# Harp_Motor_H2-module_v1_0.net
KiCad netlist of a schematic drawn in EAGLE
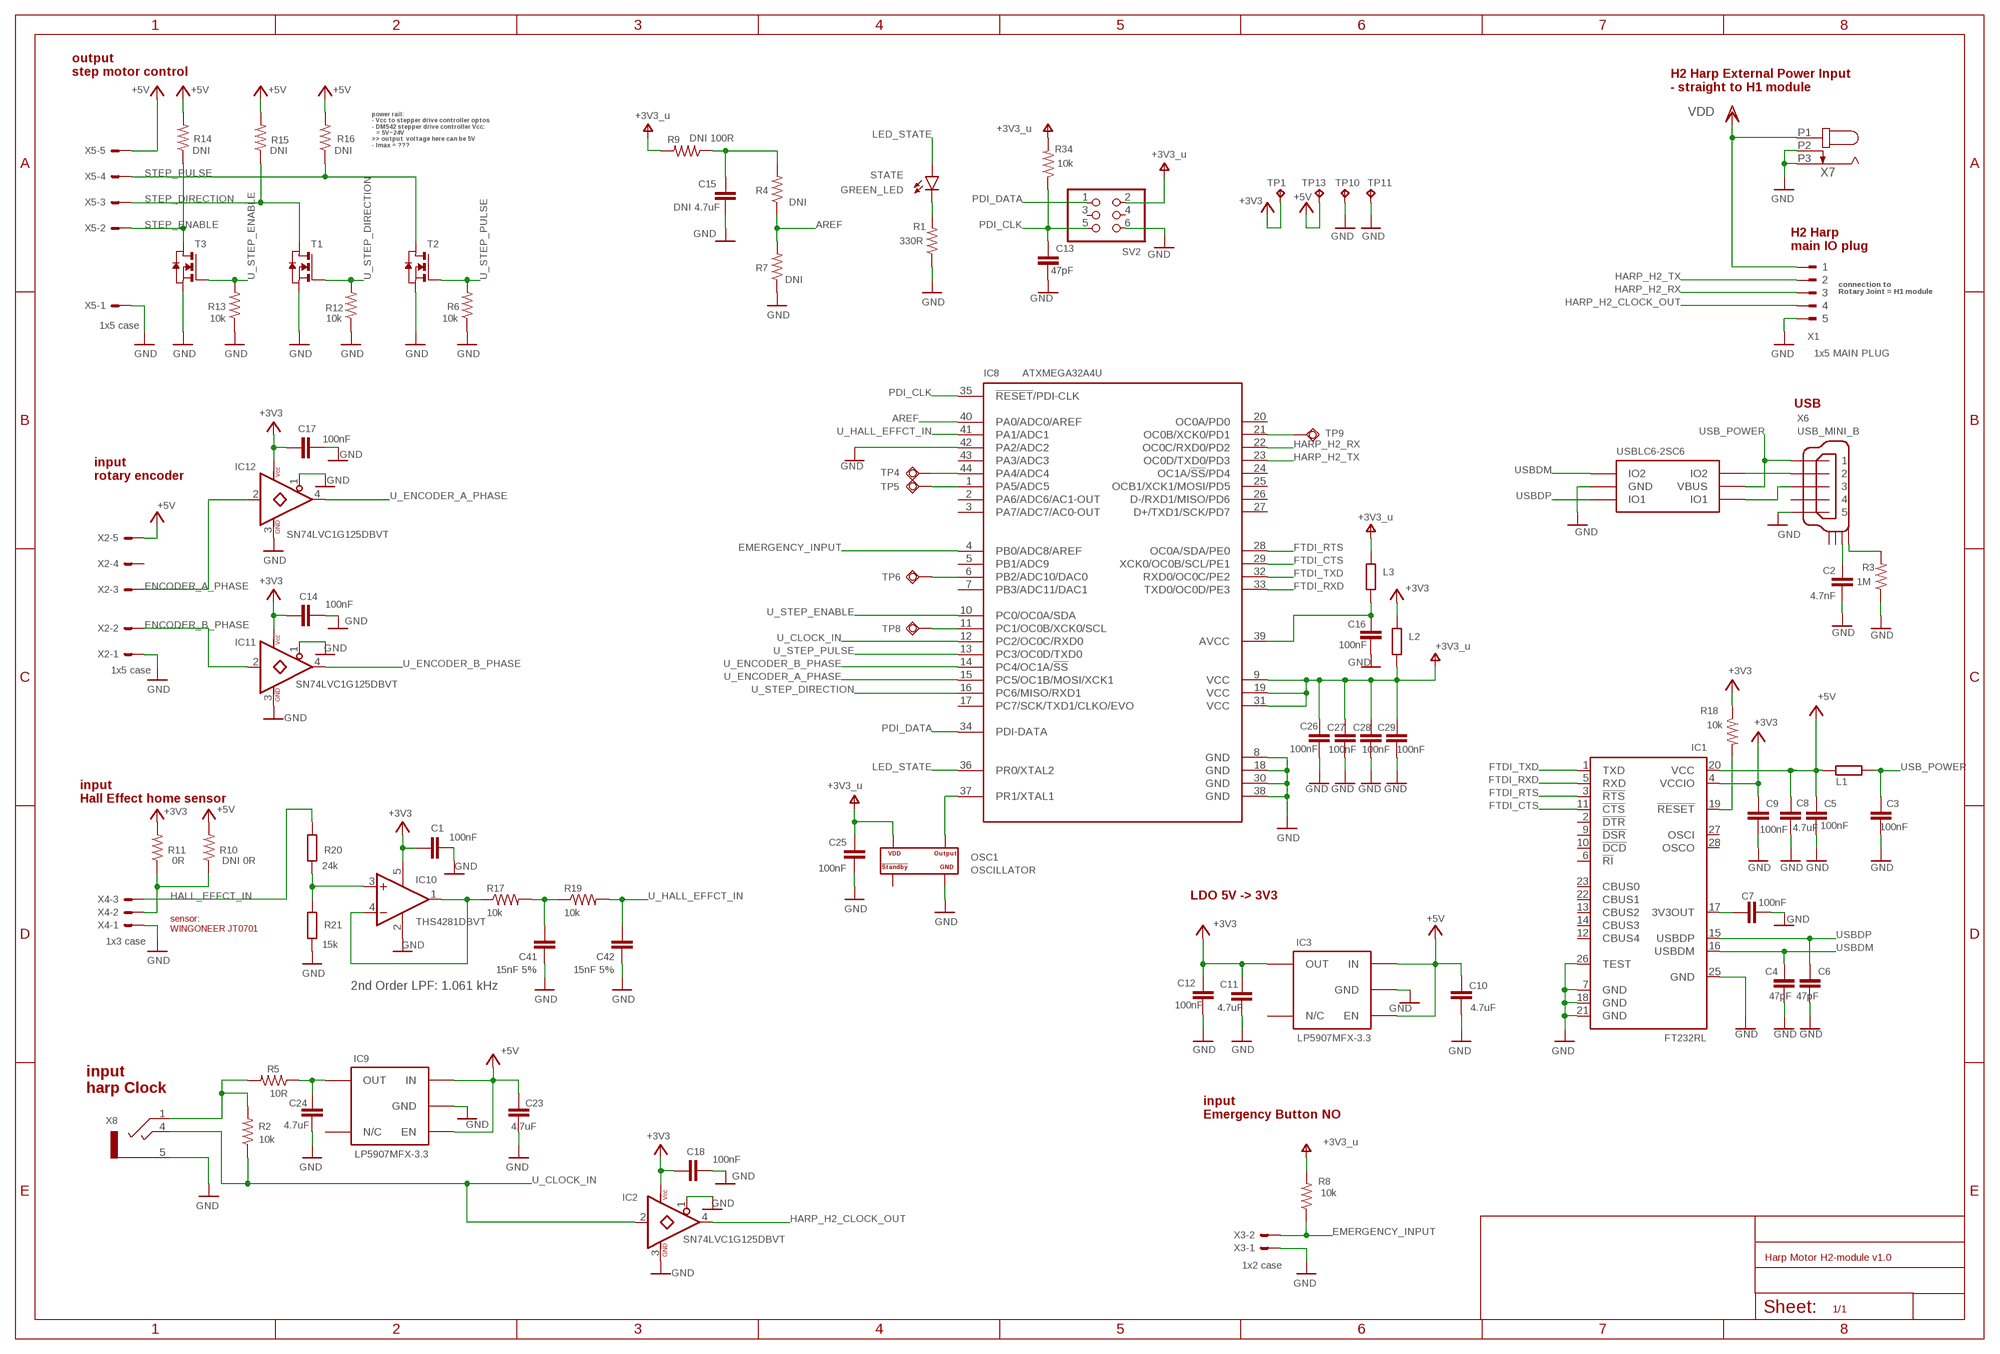
[diagram p0: schematic, sheet 1]

(export (version "E")
  (design (tool "Eeschema 10.0.6"))
  (components
    (comp (ref "C1")
      (value "100nF")
      (footprint "eagle-import:C0402K")
      (fields (field (name "MPN") "C1005X7R1H104K050BB"))
      (libsource (lib "eagle-import") (part "C-EUC0402K"))
    )
    (comp (ref "C2")
      (value "4.7nF")
      (footprint "eagle-import:C0402K")
      (fields (field (name "MPN") "CC0402KRX7R8BB472"))
      (libsource (lib "eagle-import") (part "C-EUC0402K"))
    )
    (comp (ref "C3")
      (value "100nF")
      (footprint "eagle-import:C0402K")
      (fields (field (name "MPN") "C1005X7R1H104K050BB"))
      (libsource (lib "eagle-import") (part "C-EUC0402K"))
    )
    (comp (ref "C4")
      (value "47pF")
      (footprint "eagle-import:C0402K")
      (fields (field (name "MPN") "04025A470JAT2A"))
      (libsource (lib "eagle-import") (part "C-EUC0402K"))
    )
    (comp (ref "C5")
      (value "100nF")
      (footprint "eagle-import:C0402K")
      (fields (field (name "MPN") "C1005X7R1H104K050BB"))
      (libsource (lib "eagle-import") (part "C-EUC0402K"))
    )
    (comp (ref "C6")
      (value "47pF")
      (footprint "eagle-import:C0402K")
      (fields (field (name "MPN") "04025A470JAT2A"))
      (libsource (lib "eagle-import") (part "C-EUC0402K"))
    )
    (comp (ref "C7")
      (value "100nF")
      (footprint "eagle-import:C0402K")
      (fields (field (name "MPN") "C1005X7R1H104K050BB"))
      (libsource (lib "eagle-import") (part "C-EUC0402K"))
    )
    (comp (ref "C8")
      (value "4.7uF")
      (footprint "eagle-import:C0603K")
      (fields (field (name "MPN") "C1608X6S1C475K080AC"))
      (libsource (lib "eagle-import") (part "C-EUC0603K"))
    )
    (comp (ref "C9")
      (value "100nF")
      (footprint "eagle-import:C0402K")
      (fields (field (name "MPN") "C1005X7R1H104K050BB"))
      (libsource (lib "eagle-import") (part "C-EUC0402K"))
    )
    (comp (ref "C10")
      (value "4.7uF")
      (footprint "eagle-import:C0603K")
      (fields (field (name "MPN") "C1608X6S1C475K080AC"))
      (libsource (lib "eagle-import") (part "C-EUC0603K"))
    )
    (comp (ref "C11")
      (value "4.7uF")
      (footprint "eagle-import:C0603K")
      (fields (field (name "MPN") "C1608X6S1C475K080AC"))
      (libsource (lib "eagle-import") (part "C-EUC0603K"))
    )
    (comp (ref "C12")
      (value "100nF")
      (footprint "eagle-import:C0402K")
      (fields (field (name "MPN") "C1005X7R1H104K050BB"))
      (libsource (lib "eagle-import") (part "C-EUC0402K"))
    )
    (comp (ref "C13")
      (value "47pF")
      (footprint "eagle-import:C0402K")
      (fields (field (name "MPN") "04025A470JAT2A"))
      (libsource (lib "eagle-import") (part "C-EUC0402K"))
    )
    (comp (ref "C14")
      (value "100nF")
      (footprint "eagle-import:C0402K")
      (fields (field (name "MPN") "C1005X7R1H104K050BB"))
      (libsource (lib "eagle-import") (part "C-EUC0402K"))
    )
    (comp (ref "C15")
      (value "DNI 4.7uF")
      (footprint "eagle-import:C0603K")
      (fields (field (name "MPN") "C1608X6S1C475K080AC"))
      (libsource (lib "eagle-import") (part "C-EUC0603K"))
    )
    (comp (ref "C16")
      (value "100nF")
      (footprint "eagle-import:C0402K")
      (fields (field (name "MPN") "C1005X7R1H104K050BB"))
      (libsource (lib "eagle-import") (part "C-EUC0402K"))
    )
    (comp (ref "C17")
      (value "100nF")
      (footprint "eagle-import:C0402K")
      (fields (field (name "MPN") "C1005X7R1H104K050BB"))
      (libsource (lib "eagle-import") (part "C-EUC0402K"))
    )
    (comp (ref "C18")
      (value "100nF")
      (footprint "eagle-import:C0402K")
      (fields (field (name "MPN") "C1005X7R1H104K050BB"))
      (libsource (lib "eagle-import") (part "C-EUC0402K"))
    )
    (comp (ref "C23")
      (value "4.7uF")
      (footprint "eagle-import:C0603K")
      (fields (field (name "MPN") "C1608X6S1C475K080AC"))
      (libsource (lib "eagle-import") (part "C-EUC0603K"))
    )
    (comp (ref "C24")
      (value "4.7uF")
      (footprint "eagle-import:C0603K")
      (fields (field (name "MPN") "C1608X6S1C475K080AC"))
      (libsource (lib "eagle-import") (part "C-EUC0603K"))
    )
    (comp (ref "C25")
      (value "100nF")
      (footprint "eagle-import:C0402K")
      (fields (field (name "MPN") "C1005X7R1H104K050BB"))
      (libsource (lib "eagle-import") (part "C-EUC0402K"))
    )
    (comp (ref "C26")
      (value "100nF")
      (footprint "eagle-import:C0402K")
      (fields (field (name "MPN") "C1005X7R1H104K050BB"))
      (libsource (lib "eagle-import") (part "C-EUC0402K"))
    )
    (comp (ref "C27")
      (value "100nF")
      (footprint "eagle-import:C0402K")
      (fields (field (name "MPN") "C1005X7R1H104K050BB"))
      (libsource (lib "eagle-import") (part "C-EUC0402K"))
    )
    (comp (ref "C28")
      (value "100nF")
      (footprint "eagle-import:C0402K")
      (fields (field (name "MPN") "C1005X7R1H104K050BB"))
      (libsource (lib "eagle-import") (part "C-EUC0402K"))
    )
    (comp (ref "C29")
      (value "100nF")
      (footprint "eagle-import:C0402K")
      (fields (field (name "MPN") "C1005X7R1H104K050BB"))
      (libsource (lib "eagle-import") (part "C-EUC0402K"))
    )
    (comp (ref "C41")
      (value "15nF 5%")
      (footprint "eagle-import:C0402K")
      (fields (field (name "MPN") "CGA2B3X7R1V153K050BB"))
      (libsource (lib "eagle-import") (part "C-EUC0402K"))
    )
    (comp (ref "C42")
      (value "15nF 5%")
      (footprint "eagle-import:C0402K")
      (fields (field (name "MPN") "CGA2B3X7R1V153K050BB"))
      (libsource (lib "eagle-import") (part "C-EUC0402K"))
    )
    (comp (ref "IC1")
      (value "FT232RL")
      (footprint "eagle-import:SSOP28")
      (libsource (lib "eagle-import") (part "FT232RL"))
    )
    (comp (ref "IC2")
      (value "SN74LVC1G125DBVT")
      (footprint "eagle-import:SOT23-5")
      (libsource (lib "eagle-import") (part "741G125DBVLVC"))
    )
    (comp (ref "IC3")
      (value "LP5907MFX-3.3")
      (footprint "eagle-import:TSOT23-5")
      (fields (field (name "MPN") "LP5907MFX-3.3/NOPB"))
      (libsource (lib "eagle-import") (part "TLV700XX"))
    )
    (comp (ref "IC7")
      (value "USBLC6-2SC6")
      (footprint "eagle-import:SOT23-6L")
      (libsource (lib "eagle-import") (part "USBLC6-2SC6"))
    )
    (comp (ref "IC8")
      (value "ATXMEGA32A4U")
      (footprint "eagle-import:TQFP44")
      (fields (field (name "MPN") "ATXMEGA32A4U-AUR"))
      (libsource (lib "eagle-import") (part "XMEGA-A4_AT-XMEGA-XXA4-AUTQFP44"))
    )
    (comp (ref "IC9")
      (value "LP5907MFX-3.3")
      (footprint "eagle-import:TSOT23-5")
      (fields (field (name "MPN") "LP5907MFX-3.3/NOPB"))
      (libsource (lib "eagle-import") (part "TLV700XX"))
    )
    (comp (ref "IC10")
      (value "THS4281DBVT")
      (footprint "eagle-import:SOT23-5")
      (libsource (lib "eagle-import") (part "OPA365"))
    )
    (comp (ref "IC11")
      (value "SN74LVC1G125DBVT")
      (footprint "eagle-import:SOT23-5")
      (libsource (lib "eagle-import") (part "741G125DBVLVC"))
    )
    (comp (ref "IC12")
      (value "SN74LVC1G125DBVT")
      (footprint "eagle-import:SOT23-5")
      (libsource (lib "eagle-import") (part "741G125DBVLVC"))
    )
    (comp (ref "L1")
      (value "40R@100MHz")
      (footprint "eagle-import:R0805")
      (fields (field (name "MPN") "MI0805K400R-10"))
      (libsource (lib "eagle-import") (part "R-EU_R0805"))
    )
    (comp (ref "L2")
      (value "40R@100MHz")
      (footprint "eagle-import:R0805")
      (fields (field (name "MPN") "MI0805K400R-10"))
      (libsource (lib "eagle-import") (part "R-EU_R0805"))
    )
    (comp (ref "L3")
      (value "40R@100MHz")
      (footprint "eagle-import:R0805")
      (fields (field (name "MPN") "MI0805K400R-10"))
      (libsource (lib "eagle-import") (part "R-EU_R0805"))
    )
    (comp (ref "OSC1")
      (value "OSCILLATOR")
      (footprint "eagle-import:OSCILLATOR_3.2X2.5")
      (fields (field (name "MPN") "DSC1001CI5-032.0000"))
      (libsource (lib "eagle-import") (part "OSCILLATOR"))
    )
    (comp (ref "R1")
      (value "330R")
      (footprint "eagle-import:R0402")
      (fields (field (name "MPN") "RC0402FR-07330RL"))
      (libsource (lib "eagle-import") (part "R-US_R0402"))
    )
    (comp (ref "R2")
      (value "10k")
      (footprint "eagle-import:R0402")
      (fields (field (name "MPN") "CRCW040210K0FKED"))
      (libsource (lib "eagle-import") (part "R-US_R0402"))
    )
    (comp (ref "R3")
      (value "1M")
      (footprint "eagle-import:R0402")
      (fields (field (name "MPN") "CRCW04021M00FKED"))
      (libsource (lib "eagle-import") (part "R-US_R0402"))
    )
    (comp (ref "R4")
      (value "DNI")
      (footprint "eagle-import:R0402")
      (libsource (lib "eagle-import") (part "R-US_R0402"))
    )
    (comp (ref "R5")
      (value "10R")
      (footprint "eagle-import:R0402")
      (fields (field (name "MPN") "ERJ-PA2J100X "))
      (libsource (lib "eagle-import") (part "R-US_R0402"))
    )
    (comp (ref "R6")
      (value "10k")
      (footprint "eagle-import:R0402")
      (fields (field (name "MPN") "CRCW040210K0FKED"))
      (libsource (lib "eagle-import") (part "R-US_R0402"))
    )
    (comp (ref "R7")
      (value "DNI")
      (footprint "eagle-import:R0402")
      (libsource (lib "eagle-import") (part "R-US_R0402"))
    )
    (comp (ref "R8")
      (value "10k")
      (footprint "eagle-import:R0402")
      (fields (field (name "MPN") "CRCW040210K0FKED"))
      (libsource (lib "eagle-import") (part "R-US_R0402"))
    )
    (comp (ref "R9")
      (value "DNI 100R")
      (footprint "eagle-import:R0402")
      (fields (field (name "MPN") "ERJ-2RKF1000X "))
      (libsource (lib "eagle-import") (part "R-US_R0402"))
    )
    (comp (ref "R10")
      (value "DNI 0R")
      (footprint "eagle-import:R0402")
      (fields (field (name "MPN") "RC0402JR-070RL"))
      (libsource (lib "eagle-import") (part "R-US_R0402"))
    )
    (comp (ref "R11")
      (value "0R")
      (footprint "eagle-import:R0402")
      (fields (field (name "MPN") "RC0402JR-070RL"))
      (libsource (lib "eagle-import") (part "R-US_R0402"))
    )
    (comp (ref "R12")
      (value "10k")
      (footprint "eagle-import:R0402")
      (fields (field (name "MPN") "CRCW040210K0FKED"))
      (libsource (lib "eagle-import") (part "R-US_R0402"))
    )
    (comp (ref "R13")
      (value "10k")
      (footprint "eagle-import:R0402")
      (fields (field (name "MPN") "CRCW040210K0FKED"))
      (libsource (lib "eagle-import") (part "R-US_R0402"))
    )
    (comp (ref "R14")
      (value "DNI")
      (footprint "eagle-import:R0402")
      (libsource (lib "eagle-import") (part "R-US_R0402"))
    )
    (comp (ref "R15")
      (value "DNI")
      (footprint "eagle-import:R0402")
      (libsource (lib "eagle-import") (part "R-US_R0402"))
    )
    (comp (ref "R16")
      (value "DNI")
      (footprint "eagle-import:R0402")
      (libsource (lib "eagle-import") (part "R-US_R0402"))
    )
    (comp (ref "R17")
      (value "10k")
      (footprint "eagle-import:R0402")
      (fields (field (name "MPN") "CRCW040210K0FKED"))
      (libsource (lib "eagle-import") (part "R-US_R0402"))
    )
    (comp (ref "R18")
      (value "10k")
      (footprint "eagle-import:R0402")
      (fields (field (name "MPN") "CRCW040210K0FKED"))
      (libsource (lib "eagle-import") (part "R-US_R0402"))
    )
    (comp (ref "R19")
      (value "10k")
      (footprint "eagle-import:R0402")
      (fields (field (name "MPN") "CRCW040210K0FKED"))
      (libsource (lib "eagle-import") (part "R-US_R0402"))
    )
    (comp (ref "R20")
      (value "24k")
      (footprint "eagle-import:R0402")
      (fields (field (name "MPN") "ERJ-2RKF2402X"))
      (libsource (lib "eagle-import") (part "R-EU_R0402"))
    )
    (comp (ref "R21")
      (value "15k")
      (footprint "eagle-import:R0402")
      (fields (field (name "MPN") "ERJ-2RKF1502X"))
      (libsource (lib "eagle-import") (part "R-EU_R0402"))
    )
    (comp (ref "R34")
      (value "10k")
      (footprint "eagle-import:R0402")
      (fields (field (name "MPN") "CRCW040210K0FKED"))
      (libsource (lib "eagle-import") (part "R-US_R0402"))
    )
    (comp (ref "STATE")
      (value "GREEN_LED")
      (footprint "eagle-import:CHIP-LED0603")
      (fields (field (name "MPN") "LTST-C191KGKT"))
      (libsource (lib "eagle-import") (part "LEDCHIP-LED0603"))
    )
    (comp (ref "SV2")
      (value "PINHD-2X3")
      (footprint "eagle-import:2X03")
      (fields (field (name "MPN") "609-3210-ND"))
      (libsource (lib "eagle-import") (part "PINHD-2X3"))
    )
    (comp (ref "T1")
      (value "DMG1012UW")
      (footprint "eagle-import:SOT323")
      (fields (field (name "MPN") "DMG1012UW-7"))
      (libsource (lib "eagle-import") (part "DMG1012UW-7"))
    )
    (comp (ref "T2")
      (value "DMG1012UW")
      (footprint "eagle-import:SOT323")
      (fields (field (name "MPN") "DMG1012UW-7"))
      (libsource (lib "eagle-import") (part "DMG1012UW-7"))
    )
    (comp (ref "T3")
      (value "DMG1012UW")
      (footprint "eagle-import:SOT323")
      (fields (field (name "MPN") "DMG1012UW-7"))
      (libsource (lib "eagle-import") (part "DMG1012UW-7"))
    )
    (comp (ref "TP1")
      (value "NO_COMPONENT")
      (footprint "eagle-import:B1,27")
      (libsource (lib "eagle-import") (part "TPB1,27"))
    )
    (comp (ref "TP4")
      (value "NO_COMPONENT")
      (footprint "eagle-import:TP11R")
      (libsource (lib "eagle-import") (part "TPSQTP11R"))
    )
    (comp (ref "TP5")
      (value "NO_COMPONENT")
      (footprint "eagle-import:TP11R")
      (libsource (lib "eagle-import") (part "TPSQTP11R"))
    )
    (comp (ref "TP6")
      (value "NO_COMPONENT")
      (footprint "eagle-import:TP11R")
      (libsource (lib "eagle-import") (part "TPSQTP11R"))
    )
    (comp (ref "TP8")
      (value "NO_COMPONENT")
      (footprint "eagle-import:TP11R")
      (libsource (lib "eagle-import") (part "TPSQTP11R"))
    )
    (comp (ref "TP9")
      (value "NO_COMPONENT")
      (footprint "eagle-import:TP11R")
      (libsource (lib "eagle-import") (part "TPSQTP11R"))
    )
    (comp (ref "TP10")
      (value "NO_COMPONENT")
      (footprint "eagle-import:B1,27")
      (libsource (lib "eagle-import") (part "TPB1,27"))
    )
    (comp (ref "TP11")
      (value "NO_COMPONENT")
      (footprint "eagle-import:B1,27")
      (libsource (lib "eagle-import") (part "TPB1,27"))
    )
    (comp (ref "TP13")
      (value "NO_COMPONENT")
      (footprint "eagle-import:B1,27")
      (libsource (lib "eagle-import") (part "TPB1,27"))
    )
    (comp (ref "X1")
      (value "1x5 MAIN PLUG")
      (footprint "eagle-import:90G-5")
      (fields (field (name "MPN") "20.155MH/5-E"))
      (libsource (lib "eagle-import") (part "90G-5"))
    )
    (comp (ref "X2")
      (value "1x5 case")
      (footprint "eagle-import:22-23-2051")
      (fields (field (name "MPN") "282834-5") (field (name "OEPS") "OEPS070041"))
      (libsource (lib "eagle-import") (part "22-23-2051"))
    )
    (comp (ref "X3")
      (value "1x2 case")
      (footprint "eagle-import:22-23-2021")
      (fields (field (name "MPN") "282834-2"))
      (libsource (lib "eagle-import") (part "22-23-2021"))
    )
    (comp (ref "X4")
      (value "1x3 case")
      (footprint "eagle-import:22-23-2031")
      (fields (field (name "MPN") "282834-3") (field (name "OEPS") "OEPS070035"))
      (libsource (lib "eagle-import") (part "22-23-2031"))
    )
    (comp (ref "X5")
      (value "1x5 case")
      (footprint "eagle-import:22-23-2051")
      (fields (field (name "MPN") "282834-5") (field (name "OEPS") "OEPS070041"))
      (libsource (lib "eagle-import") (part "22-23-2051"))
    )
    (comp (ref "X6")
      (value "USB_MINI_B")
      (footprint "eagle-import:240-0002-1")
      (fields (field (name "MPN") "UX60-MB-5S8"))
      (libsource (lib "eagle-import") (part "USB_MINI_B"))
    )
    (comp (ref "X7")
      (value "DC_JACK2.1MM")
      (footprint "eagle-import:DC_POWER_INPUT_2.1MM")
      (fields (field (name "MPN") "163-179PH-EX"))
      (libsource (lib "eagle-import") (part "DC_JACK2.1MM"))
    )
    (comp (ref "X8")
      (value "CLCK_JACK")
      (footprint "eagle-import:35RASMT2BHNTRX")
      (fields (field (name "MPN") "35RASMT2BHNTRX"))
      (libsource (lib "eagle-import") (part "STEREO_JACK"))
    )
  )
  (nets
    (net (code "1") (name "+3V3") (class "Default")
      (node (ref "C1") (pin "1") (pinfunction "1_1") (pintype "passive"))
      (node (ref "C11") (pin "1") (pinfunction "1_1") (pintype "passive"))
      (node (ref "C12") (pin "1") (pinfunction "1_1") (pintype "passive"))
      (node (ref "C14") (pin "1") (pinfunction "1_1") (pintype "passive"))
      (node (ref "C17") (pin "1") (pinfunction "1_1") (pintype "passive"))
      (node (ref "C18") (pin "1") (pinfunction "1_1") (pintype "passive"))
      (node (ref "C9") (pin "1") (pinfunction "1_1") (pintype "passive"))
      (node (ref "IC1") (pin "4") (pinfunction "VCCIO_4") (pintype "power_in"))
      (node (ref "IC10") (pin "5") (pinfunction "V+_5") (pintype "power_in"))
      (node (ref "IC11") (pin "5") (pinfunction "VCC_5") (pintype "passive"))
      (node (ref "IC12") (pin "5") (pinfunction "VCC_5") (pintype "passive"))
      (node (ref "IC2") (pin "5") (pinfunction "VCC_5") (pintype "passive"))
      (node (ref "IC3") (pin "5") (pinfunction "OUT_5") (pintype "bidirectional"))
      (node (ref "L2") (pin "2") (pinfunction "2_2") (pintype "passive"))
      (node (ref "R11") (pin "2") (pinfunction "2_2") (pintype "passive"))
      (node (ref "R18") (pin "1") (pinfunction "1_1") (pintype "passive"))
      (node (ref "TP1") (pin "TP") (pinfunction "TP_TP") (pintype "input"))
    )
    (net (code "2") (name "+3V3_u") (class "Default")
      (node (ref "C25") (pin "1") (pinfunction "1_1") (pintype "passive"))
      (node (ref "C26") (pin "1") (pinfunction "1_1") (pintype "passive"))
      (node (ref "C27") (pin "1") (pinfunction "1_1") (pintype "passive"))
      (node (ref "C28") (pin "1") (pinfunction "1_1") (pintype "passive"))
      (node (ref "C29") (pin "1") (pinfunction "1_1") (pintype "passive"))
      (node (ref "IC8") (pin "19") (pinfunction "VCC_19") (pintype "power_in"))
      (node (ref "IC8") (pin "31") (pinfunction "VCC_31") (pintype "power_in"))
      (node (ref "IC8") (pin "9") (pinfunction "VCC_9") (pintype "power_in"))
      (node (ref "L2") (pin "1") (pinfunction "1_1") (pintype "passive"))
      (node (ref "L3") (pin "2") (pinfunction "2_2") (pintype "passive"))
      (node (ref "OSC1") (pin "P$4") (pinfunction "VDD_P$4") (pintype "passive"))
      (node (ref "R34") (pin "2") (pinfunction "2_2") (pintype "passive"))
      (node (ref "R8") (pin "2") (pinfunction "2_2") (pintype "passive"))
      (node (ref "R9") (pin "2") (pinfunction "2_2") (pintype "passive"))
      (node (ref "SV2") (pin "2") (pinfunction "2_2") (pintype "passive"))
    )
    (net (code "3") (name "+5V") (class "Default")
      (node (ref "C10") (pin "1") (pinfunction "1_1") (pintype "passive"))
      (node (ref "C23") (pin "1") (pinfunction "1_1") (pintype "passive"))
      (node (ref "C5") (pin "1") (pinfunction "1_1") (pintype "passive"))
      (node (ref "C8") (pin "1") (pinfunction "1_1") (pintype "passive"))
      (node (ref "IC1") (pin "20") (pinfunction "VCC_20") (pintype "power_in"))
      (node (ref "IC3") (pin "1") (pinfunction "IN_1") (pintype "bidirectional"))
      (node (ref "IC3") (pin "3") (pinfunction "EN_3") (pintype "bidirectional"))
      (node (ref "IC9") (pin "1") (pinfunction "IN_1") (pintype "bidirectional"))
      (node (ref "IC9") (pin "3") (pinfunction "EN_3") (pintype "bidirectional"))
      (node (ref "L1") (pin "1") (pinfunction "1_1") (pintype "passive"))
      (node (ref "R10") (pin "2") (pinfunction "2_2") (pintype "passive"))
      (node (ref "R14") (pin "2") (pinfunction "2_2") (pintype "passive"))
      (node (ref "R15") (pin "2") (pinfunction "2_2") (pintype "passive"))
      (node (ref "R16") (pin "2") (pinfunction "2_2") (pintype "passive"))
      (node (ref "TP13") (pin "TP") (pinfunction "TP_TP") (pintype "input"))
      (node (ref "X2") (pin "5") (pinfunction "S_5") (pintype "passive"))
      (node (ref "X5") (pin "5") (pinfunction "S_5") (pintype "passive"))
    )
    (net (code "4") (name "/AREF") (class "Default")
      (node (ref "IC8") (pin "40") (pinfunction "PA0/ADC0/AREF_40") (pintype "bidirectional"))
      (node (ref "R4") (pin "1") (pinfunction "1_1") (pintype "passive"))
      (node (ref "R7") (pin "2") (pinfunction "2_2") (pintype "passive"))
    )
    (net (code "5") (name "/EMERGENCY_INPUT") (class "Default")
      (node (ref "IC8") (pin "4") (pinfunction "PB0/ADC8/AREF_4") (pintype "bidirectional"))
      (node (ref "R8") (pin "1") (pinfunction "1_1") (pintype "passive"))
      (node (ref "X3") (pin "2") (pinfunction "S_2") (pintype "passive"))
    )
    (net (code "6") (name "/ENCODER_A_PHASE") (class "Default")
      (node (ref "IC12") (pin "2") (pinfunction "I_2") (pintype "input"))
      (node (ref "X2") (pin "3") (pinfunction "S_3") (pintype "passive"))
    )
    (net (code "7") (name "/ENCODER_B_PHASE") (class "Default")
      (node (ref "IC11") (pin "2") (pinfunction "I_2") (pintype "input"))
      (node (ref "X2") (pin "2") (pinfunction "S_2") (pintype "passive"))
    )
    (net (code "8") (name "/FTDI_CTS") (class "Default")
      (node (ref "IC1") (pin "11") (pinfunction "~{CTS}_11") (pintype "input"))
      (node (ref "IC8") (pin "29") (pinfunction "XCK0/OC0B/SCL/PE1_29") (pintype "bidirectional"))
    )
    (net (code "9") (name "/FTDI_RTS") (class "Default")
      (node (ref "IC1") (pin "3") (pinfunction "~{RTS}_3") (pintype "output"))
      (node (ref "IC8") (pin "28") (pinfunction "OC0A/SDA/PE0_28") (pintype "bidirectional"))
    )
    (net (code "10") (name "/FTDI_RXD") (class "Default")
      (node (ref "IC1") (pin "5") (pinfunction "RXD_5") (pintype "input"))
      (node (ref "IC8") (pin "33") (pinfunction "TXD0/OC0D/PE3_33") (pintype "bidirectional"))
    )
    (net (code "11") (name "/FTDI_TXD") (class "Default")
      (node (ref "IC1") (pin "1") (pinfunction "TXD_1") (pintype "output"))
      (node (ref "IC8") (pin "32") (pinfunction "RXD0/OC0C/PE2_32") (pintype "bidirectional"))
    )
    (net (code "12") (name "/HALL_EFFCT_IN") (class "Default")
      (node (ref "R20") (pin "2") (pinfunction "2_2") (pintype "passive"))
      (node (ref "X4") (pin "3") (pinfunction "S_3") (pintype "passive"))
    )
    (net (code "13") (name "/HARP_H2_CLOCK_OUT") (class "Default")
      (node (ref "IC2") (pin "4") (pinfunction "O_4") (pintype "tri_state"))
      (node (ref "X1") (pin "4") (pinfunction "4_4") (pintype "passive"))
    )
    (net (code "14") (name "/HARP_H2_RX") (class "Default")
      (node (ref "IC8") (pin "22") (pinfunction "OC0C/RXD0/PD2_22") (pintype "bidirectional"))
      (node (ref "X1") (pin "3") (pinfunction "3_3") (pintype "passive"))
    )
    (net (code "15") (name "/HARP_H2_TX") (class "Default")
      (node (ref "IC8") (pin "23") (pinfunction "OC0D/TXD0/PD3_23") (pintype "bidirectional"))
      (node (ref "X1") (pin "2") (pinfunction "2_2") (pintype "passive"))
    )
    (net (code "16") (name "/LED_STATE") (class "Default")
      (node (ref "IC8") (pin "36") (pinfunction "PR0/XTAL2_36") (pintype "bidirectional"))
      (node (ref "STATE") (pin "A") (pinfunction "A_A") (pintype "passive"))
    )
    (net (code "17") (name "/PDI_CLK") (class "Default")
      (node (ref "C13") (pin "1") (pinfunction "1_1") (pintype "passive"))
      (node (ref "IC8") (pin "35") (pinfunction "~{RESET}/PDI-CLK_35") (pintype "input"))
      (node (ref "R34") (pin "1") (pinfunction "1_1") (pintype "passive"))
      (node (ref "SV2") (pin "5") (pinfunction "5_5") (pintype "passive"))
    )
    (net (code "18") (name "/PDI_DATA") (class "Default")
      (node (ref "IC8") (pin "34") (pinfunction "PDI-DATA_34") (pintype "bidirectional"))
      (node (ref "SV2") (pin "1") (pinfunction "1_1") (pintype "passive"))
    )
    (net (code "19") (name "/STEP_DIRECTION") (class "Default")
      (node (ref "R15") (pin "1") (pinfunction "1_1") (pintype "passive"))
      (node (ref "T1") (pin "3") (pinfunction "D_3") (pintype "passive"))
      (node (ref "X5") (pin "3") (pinfunction "S_3") (pintype "passive"))
    )
    (net (code "20") (name "/STEP_ENABLE") (class "Default")
      (node (ref "R14") (pin "1") (pinfunction "1_1") (pintype "passive"))
      (node (ref "T3") (pin "3") (pinfunction "D_3") (pintype "passive"))
      (node (ref "X5") (pin "2") (pinfunction "S_2") (pintype "passive"))
    )
    (net (code "21") (name "/STEP_PULSE") (class "Default")
      (node (ref "R16") (pin "1") (pinfunction "1_1") (pintype "passive"))
      (node (ref "T2") (pin "3") (pinfunction "D_3") (pintype "passive"))
      (node (ref "X5") (pin "4") (pinfunction "S_4") (pintype "passive"))
    )
    (net (code "22") (name "/USBDM") (class "Default")
      (node (ref "C4") (pin "1") (pinfunction "1_1") (pintype "passive"))
      (node (ref "IC1") (pin "16") (pinfunction "USBDM_16") (pintype "bidirectional"))
      (node (ref "IC7") (pin "P$3") (pinfunction "IO2_P$3") (pintype "bidirectional"))
    )
    (net (code "23") (name "/USBDP") (class "Default")
      (node (ref "C6") (pin "1") (pinfunction "1_1") (pintype "passive"))
      (node (ref "IC1") (pin "15") (pinfunction "USBDP_15") (pintype "bidirectional"))
      (node (ref "IC7") (pin "P$1") (pinfunction "IO1_P$1") (pintype "bidirectional"))
    )
    (net (code "24") (name "/USB_POWER") (class "Default")
      (node (ref "C3") (pin "1") (pinfunction "1_1") (pintype "passive"))
      (node (ref "IC7") (pin "P$5") (pinfunction "VBUS_P$5") (pintype "bidirectional"))
      (node (ref "L1") (pin "2") (pinfunction "2_2") (pintype "passive"))
      (node (ref "X6") (pin "P$1") (pinfunction "1_P$1") (pintype "bidirectional"))
    )
    (net (code "25") (name "/U_CLOCK_IN") (class "Default")
      (node (ref "IC2") (pin "2") (pinfunction "I_2") (pintype "input"))
      (node (ref "IC8") (pin "12") (pinfunction "PC2/OC0C/RXD0_12") (pintype "bidirectional"))
      (node (ref "R2") (pin "1") (pinfunction "1_1") (pintype "passive"))
      (node (ref "X8") (pin "4") (pinfunction "4_4") (pintype "passive"))
    )
    (net (code "26") (name "/U_ENCODER_A_PHASE") (class "Default")
      (node (ref "IC12") (pin "4") (pinfunction "O_4") (pintype "tri_state"))
      (node (ref "IC8") (pin "15") (pinfunction "PC5/OC1B/MOSI/XCK1_15") (pintype "bidirectional"))
    )
    (net (code "27") (name "/U_ENCODER_B_PHASE") (class "Default")
      (node (ref "IC11") (pin "4") (pinfunction "O_4") (pintype "tri_state"))
      (node (ref "IC8") (pin "14") (pinfunction "PC4/OC1A/~{SS}_14") (pintype "bidirectional"))
    )
    (net (code "28") (name "/U_HALL_EFFCT_IN") (class "Default")
      (node (ref "C42") (pin "2") (pinfunction "2_2") (pintype "passive"))
      (node (ref "IC8") (pin "41") (pinfunction "PA1/ADC1_41") (pintype "bidirectional"))
      (node (ref "R19") (pin "2") (pinfunction "2_2") (pintype "passive"))
    )
    (net (code "29") (name "/U_STEP_DIRECTION") (class "Default")
      (node (ref "IC8") (pin "16") (pinfunction "PC6/MISO/RXD1_16") (pintype "bidirectional"))
      (node (ref "R12") (pin "2") (pinfunction "2_2") (pintype "passive"))
      (node (ref "T1") (pin "1") (pinfunction "G_1") (pintype "passive"))
    )
    (net (code "30") (name "/U_STEP_ENABLE") (class "Default")
      (node (ref "IC8") (pin "10") (pinfunction "PC0/OC0A/SDA_10") (pintype "bidirectional"))
      (node (ref "R13") (pin "2") (pinfunction "2_2") (pintype "passive"))
      (node (ref "T3") (pin "1") (pinfunction "G_1") (pintype "passive"))
    )
    (net (code "31") (name "/U_STEP_PULSE") (class "Default")
      (node (ref "IC8") (pin "13") (pinfunction "PC3/OC0D/TXD0_13") (pintype "bidirectional"))
      (node (ref "R6") (pin "2") (pinfunction "2_2") (pintype "passive"))
      (node (ref "T2") (pin "1") (pinfunction "G_1") (pintype "passive"))
    )
    (net (code "32") (name "GND") (class "Default")
      (node (ref "C1") (pin "2") (pinfunction "2_2") (pintype "passive"))
      (node (ref "C10") (pin "2") (pinfunction "2_2") (pintype "passive"))
      (node (ref "C11") (pin "2") (pinfunction "2_2") (pintype "passive"))
      (node (ref "C12") (pin "2") (pinfunction "2_2") (pintype "passive"))
      (node (ref "C13") (pin "2") (pinfunction "2_2") (pintype "passive"))
      (node (ref "C14") (pin "2") (pinfunction "2_2") (pintype "passive"))
      (node (ref "C15") (pin "2") (pinfunction "2_2") (pintype "passive"))
      (node (ref "C16") (pin "2") (pinfunction "2_2") (pintype "passive"))
      (node (ref "C17") (pin "2") (pinfunction "2_2") (pintype "passive"))
      (node (ref "C18") (pin "2") (pinfunction "2_2") (pintype "passive"))
      (node (ref "C2") (pin "2") (pinfunction "2_2") (pintype "passive"))
      (node (ref "C23") (pin "2") (pinfunction "2_2") (pintype "passive"))
      (node (ref "C24") (pin "2") (pinfunction "2_2") (pintype "passive"))
      (node (ref "C25") (pin "2") (pinfunction "2_2") (pintype "passive"))
      (node (ref "C26") (pin "2") (pinfunction "2_2") (pintype "passive"))
      (node (ref "C27") (pin "2") (pinfunction "2_2") (pintype "passive"))
      (node (ref "C28") (pin "2") (pinfunction "2_2") (pintype "passive"))
      (node (ref "C29") (pin "2") (pinfunction "2_2") (pintype "passive"))
      (node (ref "C3") (pin "2") (pinfunction "2_2") (pintype "passive"))
      (node (ref "C4") (pin "2") (pinfunction "2_2") (pintype "passive"))
      (node (ref "C41") (pin "1") (pinfunction "1_1") (pintype "passive"))
      (node (ref "C42") (pin "1") (pinfunction "1_1") (pintype "passive"))
      (node (ref "C5") (pin "2") (pinfunction "2_2") (pintype "passive"))
      (node (ref "C6") (pin "2") (pinfunction "2_2") (pintype "passive"))
      (node (ref "C7") (pin "2") (pinfunction "2_2") (pintype "passive"))
      (node (ref "C8") (pin "2") (pinfunction "2_2") (pintype "passive"))
      (node (ref "C9") (pin "2") (pinfunction "2_2") (pintype "passive"))
      (node (ref "IC1") (pin "18") (pinfunction "GND_18") (pintype "power_in"))
      (node (ref "IC1") (pin "21") (pinfunction "GND_21") (pintype "power_in"))
      (node (ref "IC1") (pin "25") (pinfunction "GND_25") (pintype "power_in"))
      (node (ref "IC1") (pin "26") (pinfunction "TEST_26") (pintype "input"))
      (node (ref "IC1") (pin "7") (pinfunction "GND_7") (pintype "power_in"))
      (node (ref "IC10") (pin "2") (pinfunction "V-_2") (pintype "power_in"))
      (node (ref "IC11") (pin "1") (pinfunction "OE_1") (pintype "input"))
      (node (ref "IC11") (pin "3") (pinfunction "GND_3") (pintype "power_in"))
      (node (ref "IC12") (pin "1") (pinfunction "OE_1") (pintype "input"))
      (node (ref "IC12") (pin "3") (pinfunction "GND_3") (pintype "power_in"))
      (node (ref "IC2") (pin "1") (pinfunction "OE_1") (pintype "input"))
      (node (ref "IC2") (pin "3") (pinfunction "GND_3") (pintype "power_in"))
      (node (ref "IC3") (pin "2") (pinfunction "GND_2") (pintype "bidirectional"))
      (node (ref "IC7") (pin "P$2") (pinfunction "GND_P$2") (pintype "bidirectional"))
      (node (ref "IC8") (pin "18") (pinfunction "GND_18") (pintype "power_in"))
      (node (ref "IC8") (pin "30") (pinfunction "GND_30") (pintype "power_in"))
      (node (ref "IC8") (pin "38") (pinfunction "GND_38") (pintype "power_in"))
      (node (ref "IC8") (pin "42") (pinfunction "PA2/ADC2_42") (pintype "bidirectional"))
      (node (ref "IC8") (pin "8") (pinfunction "GND_8") (pintype "power_in"))
      (node (ref "IC9") (pin "2") (pinfunction "GND_2") (pintype "bidirectional"))
      (node (ref "OSC1") (pin "P$2") (pinfunction "GND_P$2") (pintype "passive"))
      (node (ref "R1") (pin "1") (pinfunction "1_1") (pintype "passive"))
      (node (ref "R12") (pin "1") (pinfunction "1_1") (pintype "passive"))
      (node (ref "R13") (pin "1") (pinfunction "1_1") (pintype "passive"))
      (node (ref "R21") (pin "1") (pinfunction "1_1") (pintype "passive"))
      (node (ref "R3") (pin "1") (pinfunction "1_1") (pintype "passive"))
      (node (ref "R6") (pin "1") (pinfunction "1_1") (pintype "passive"))
      (node (ref "R7") (pin "1") (pinfunction "1_1") (pintype "passive"))
      (node (ref "SV2") (pin "6") (pinfunction "6_6") (pintype "passive"))
      (node (ref "T1") (pin "2") (pinfunction "S_2") (pintype "passive"))
      (node (ref "T2") (pin "2") (pinfunction "S_2") (pintype "passive"))
      (node (ref "T3") (pin "2") (pinfunction "S_2") (pintype "passive"))
      (node (ref "TP10") (pin "TP") (pinfunction "TP_TP") (pintype "input"))
      (node (ref "TP11") (pin "TP") (pinfunction "TP_TP") (pintype "input"))
      (node (ref "X1") (pin "5") (pinfunction "5_5") (pintype "passive"))
      (node (ref "X2") (pin "1") (pinfunction "S_1") (pintype "passive"))
      (node (ref "X3") (pin "1") (pinfunction "S_1") (pintype "passive"))
      (node (ref "X4") (pin "1") (pinfunction "S_1") (pintype "passive"))
      (node (ref "X5") (pin "1") (pinfunction "S_1") (pintype "passive"))
      (node (ref "X6") (pin "P$5") (pinfunction "5_P$5") (pintype "bidirectional"))
      (node (ref "X7") (pin "P2") (pinfunction "2_P2") (pintype "passive"))
      (node (ref "X7") (pin "P3") (pinfunction "3_P3") (pintype "passive"))
      (node (ref "X8") (pin "5") (pinfunction "5_5") (pintype "passive"))
    )
    (net (code "33") (name "Net-(C15-Pad1)") (class "Default")
      (node (ref "C15") (pin "1") (pinfunction "1_1") (pintype "passive"))
      (node (ref "R4") (pin "2") (pinfunction "2_2") (pintype "passive"))
      (node (ref "R9") (pin "1") (pinfunction "1_1") (pintype "passive"))
    )
    (net (code "34") (name "Net-(C41-Pad2)") (class "Default")
      (node (ref "C41") (pin "2") (pinfunction "2_2") (pintype "passive"))
      (node (ref "R17") (pin "2") (pinfunction "2_2") (pintype "passive"))
      (node (ref "R19") (pin "1") (pinfunction "1_1") (pintype "passive"))
    )
    (net (code "35") (name "Net-(IC1-3V3OUT)") (class "Default")
      (node (ref "C7") (pin "1") (pinfunction "1_1") (pintype "passive"))
      (node (ref "IC1") (pin "17") (pinfunction "3V3OUT_17") (pintype "output"))
    )
    (net (code "36") (name "Net-(IC1-~{RESET})") (class "Default")
      (node (ref "IC1") (pin "19") (pinfunction "~{RESET}_19") (pintype "input"))
      (node (ref "R18") (pin "2") (pinfunction "2_2") (pintype "passive"))
    )
    (net (code "37") (name "Net-(IC8-AVCC)") (class "Default")
      (node (ref "C16") (pin "1") (pinfunction "1_1") (pintype "passive"))
      (node (ref "IC8") (pin "39") (pinfunction "AVCC_39") (pintype "power_in"))
      (node (ref "L3") (pin "1") (pinfunction "1_1") (pintype "passive"))
    )
    (net (code "38") (name "Net-(IC8-OC0B{slash}XCK0{slash}PD1)") (class "Default")
      (node (ref "IC8") (pin "21") (pinfunction "OC0B/XCK0/PD1_21") (pintype "bidirectional"))
      (node (ref "TP9") (pin "TP") (pinfunction "TP_TP") (pintype "input"))
    )
    (net (code "39") (name "Net-(IC8-PA4{slash}ADC4)") (class "Default")
      (node (ref "IC8") (pin "44") (pinfunction "PA4/ADC4_44") (pintype "bidirectional"))
      (node (ref "TP4") (pin "TP") (pinfunction "TP_TP") (pintype "input"))
    )
    (net (code "40") (name "Net-(IC8-PA5{slash}ADC5)") (class "Default")
      (node (ref "IC8") (pin "1") (pinfunction "PA5/ADC5_1") (pintype "bidirectional"))
      (node (ref "TP5") (pin "TP") (pinfunction "TP_TP") (pintype "input"))
    )
    (net (code "41") (name "Net-(IC8-PB2{slash}ADC10{slash}DAC0)") (class "Default")
      (node (ref "IC8") (pin "6") (pinfunction "PB2/ADC10/DAC0_6") (pintype "bidirectional"))
      (node (ref "TP6") (pin "TP") (pinfunction "TP_TP") (pintype "input"))
    )
    (net (code "42") (name "Net-(IC8-PC1{slash}OC0B{slash}XCK0{slash}SCL)") (class "Default")
      (node (ref "IC8") (pin "11") (pinfunction "PC1/OC0B/XCK0/SCL_11") (pintype "bidirectional"))
      (node (ref "TP8") (pin "TP") (pinfunction "TP_TP") (pintype "input"))
    )
    (net (code "43") (name "Net-(IC8-PR1{slash}XTAL1)") (class "Default")
      (node (ref "IC8") (pin "37") (pinfunction "PR1/XTAL1_37") (pintype "bidirectional"))
      (node (ref "OSC1") (pin "P$3") (pinfunction "OUTPUT_P$3") (pintype "passive"))
    )
    (net (code "44") (name "Net-(IC9-OUT)") (class "Default")
      (node (ref "C24") (pin "1") (pinfunction "1_1") (pintype "passive"))
      (node (ref "IC9") (pin "5") (pinfunction "OUT_5") (pintype "bidirectional"))
      (node (ref "R5") (pin "1") (pinfunction "1_1") (pintype "passive"))
    )
    (net (code "45") (name "Net-(IC10-+IN)") (class "Default")
      (node (ref "IC10") (pin "3") (pinfunction "+IN_3") (pintype "input"))
      (node (ref "R20") (pin "1") (pinfunction "1_1") (pintype "passive"))
      (node (ref "R21") (pin "2") (pinfunction "2_2") (pintype "passive"))
    )
    (net (code "46") (name "Net-(IC10--IN)") (class "Default")
      (node (ref "IC10") (pin "1") (pinfunction "OUT_1") (pintype "output"))
      (node (ref "IC10") (pin "4") (pinfunction "-IN_4") (pintype "input"))
      (node (ref "R17") (pin "1") (pinfunction "1_1") (pintype "passive"))
    )
    (net (code "47") (name "Net-(R1-Pad2)") (class "Default")
      (node (ref "R1") (pin "2") (pinfunction "2_2") (pintype "passive"))
      (node (ref "STATE") (pin "C") (pinfunction "C_C") (pintype "passive"))
    )
    (net (code "48") (name "Net-(R2-Pad2)") (class "Default")
      (node (ref "R2") (pin "2") (pinfunction "2_2") (pintype "passive"))
      (node (ref "R5") (pin "2") (pinfunction "2_2") (pintype "passive"))
      (node (ref "X8") (pin "1") (pinfunction "1_1") (pintype "passive"))
    )
    (net (code "49") (name "Net-(X4B-S)") (class "Default")
      (node (ref "R10") (pin "1") (pinfunction "1_1") (pintype "passive"))
      (node (ref "R11") (pin "1") (pinfunction "1_1") (pintype "passive"))
      (node (ref "X4") (pin "2") (pinfunction "S_2") (pintype "passive"))
    )
    (net (code "50") (name "Net-(X6-2)") (class "Default")
      (node (ref "IC7") (pin "P$4") (pinfunction "IO2_P$4") (pintype "bidirectional"))
      (node (ref "X6") (pin "P$2") (pinfunction "2_P$2") (pintype "bidirectional"))
    )
    (net (code "51") (name "Net-(X6-3)") (class "Default")
      (node (ref "IC7") (pin "P$6") (pinfunction "IO1_P$6") (pintype "bidirectional"))
      (node (ref "X6") (pin "P$3") (pinfunction "3_P$3") (pintype "bidirectional"))
    )
    (net (code "52") (name "Net-(X6-P$3)") (class "Default")
      (node (ref "C2") (pin "1") (pinfunction "1_1") (pintype "passive"))
      (node (ref "X6") (pin "SHIELD_3") (pinfunction "P$3_SHIELD_3") (pintype "bidirectional"))
    )
    (net (code "53") (name "Net-(X6-P$4)") (class "Default")
      (node (ref "R3") (pin "2") (pinfunction "2_2") (pintype "passive"))
      (node (ref "X6") (pin "SHIELD_4") (pinfunction "P$4_SHIELD_4") (pintype "bidirectional"))
    )
    (net (code "54") (name "VDD") (class "Default")
      (node (ref "X1") (pin "1") (pinfunction "1_1") (pintype "passive"))
      (node (ref "X7") (pin "P1") (pinfunction "1_P1") (pintype "passive"))
    )
    (net (code "55") (name "unconnected-(IC1-CBUS0-Pad23)") (class "Default")
      (node (ref "IC1") (pin "23") (pinfunction "CBUS0_23") (pintype "bidirectional"))
    )
    (net (code "56") (name "unconnected-(IC1-CBUS1-Pad22)") (class "Default")
      (node (ref "IC1") (pin "22") (pinfunction "CBUS1_22") (pintype "bidirectional"))
    )
    (net (code "57") (name "unconnected-(IC1-CBUS2-Pad13)") (class "Default")
      (node (ref "IC1") (pin "13") (pinfunction "CBUS2_13") (pintype "bidirectional"))
    )
    (net (code "58") (name "unconnected-(IC1-CBUS3-Pad14)") (class "Default")
      (node (ref "IC1") (pin "14") (pinfunction "CBUS3_14") (pintype "bidirectional"))
    )
    (net (code "59") (name "unconnected-(IC1-CBUS4-Pad12)") (class "Default")
      (node (ref "IC1") (pin "12") (pinfunction "CBUS4_12") (pintype "bidirectional"))
    )
    (net (code "60") (name "unconnected-(IC1-OSCI-Pad27)") (class "Default")
      (node (ref "IC1") (pin "27") (pinfunction "OSCI_27") (pintype "input"))
    )
    (net (code "61") (name "unconnected-(IC1-OSCO-Pad28)") (class "Default")
      (node (ref "IC1") (pin "28") (pinfunction "OSCO_28") (pintype "output"))
    )
    (net (code "62") (name "unconnected-(IC1-~{DCD}-Pad10)") (class "Default")
      (node (ref "IC1") (pin "10") (pinfunction "~{DCD}_10") (pintype "input"))
    )
    (net (code "63") (name "unconnected-(IC1-~{DSR}-Pad9)") (class "Default")
      (node (ref "IC1") (pin "9") (pinfunction "~{DSR}_9") (pintype "input"))
    )
    (net (code "64") (name "unconnected-(IC1-~{DTR}-Pad2)") (class "Default")
      (node (ref "IC1") (pin "2") (pinfunction "~{DTR}_2") (pintype "output"))
    )
    (net (code "65") (name "unconnected-(IC1-~{RI}-Pad6)") (class "Default")
      (node (ref "IC1") (pin "6") (pinfunction "~{RI}_6") (pintype "input"))
    )
    (net (code "66") (name "unconnected-(IC3-N{slash}C-Pad4)") (class "Default")
      (node (ref "IC3") (pin "4") (pinfunction "N/C_4") (pintype "bidirectional"))
    )
    (net (code "67") (name "unconnected-(IC8-D+{slash}TXD1{slash}SCK{slash}PD7-Pad27)") (class "Default")
      (node (ref "IC8") (pin "27") (pinfunction "D+/TXD1/SCK/PD7_27") (pintype "bidirectional"))
    )
    (net (code "68") (name "unconnected-(IC8-D-{slash}RXD1{slash}MISO{slash}PD6-Pad26)") (class "Default")
      (node (ref "IC8") (pin "26") (pinfunction "D-/RXD1/MISO/PD6_26") (pintype "bidirectional"))
    )
    (net (code "69") (name "unconnected-(IC8-OC0A{slash}PD0-Pad20)") (class "Default")
      (node (ref "IC8") (pin "20") (pinfunction "OC0A/PD0_20") (pintype "bidirectional"))
    )
    (net (code "70") (name "unconnected-(IC8-OC1A{slash}~{SS}{slash}PD4-Pad24)") (class "Default")
      (node (ref "IC8") (pin "24") (pinfunction "OC1A/~{SS}/PD4_24") (pintype "bidirectional"))
    )
    (net (code "71") (name "unconnected-(IC8-OCB1{slash}XCK1{slash}MOSI{slash}PD5-Pad25)") (class "Default")
      (node (ref "IC8") (pin "25") (pinfunction "OCB1/XCK1/MOSI/PD5_25") (pintype "bidirectional"))
    )
    (net (code "72") (name "unconnected-(IC8-PA3{slash}ADC3-Pad43)") (class "Default")
      (node (ref "IC8") (pin "43") (pinfunction "PA3/ADC3_43") (pintype "bidirectional"))
    )
    (net (code "73") (name "unconnected-(IC8-PA6{slash}ADC6{slash}AC1-OUT-Pad2)") (class "Default")
      (node (ref "IC8") (pin "2") (pinfunction "PA6/ADC6/AC1-OUT_2") (pintype "bidirectional"))
    )
    (net (code "74") (name "unconnected-(IC8-PA7{slash}ADC7{slash}AC0-OUT-Pad3)") (class "Default")
      (node (ref "IC8") (pin "3") (pinfunction "PA7/ADC7/AC0-OUT_3") (pintype "bidirectional"))
    )
    (net (code "75") (name "unconnected-(IC8-PB1{slash}ADC9-Pad5)") (class "Default")
      (node (ref "IC8") (pin "5") (pinfunction "PB1/ADC9_5") (pintype "bidirectional"))
    )
    (net (code "76") (name "unconnected-(IC8-PB3{slash}ADC11{slash}DAC1-Pad7)") (class "Default")
      (node (ref "IC8") (pin "7") (pinfunction "PB3/ADC11/DAC1_7") (pintype "bidirectional"))
    )
    (net (code "77") (name "unconnected-(IC8-PC7{slash}SCK{slash}TXD1{slash}CLKO{slash}EVO-Pad17)") (class "Default")
      (node (ref "IC8") (pin "17") (pinfunction "PC7/SCK/TXD1/CLKO/EVO_17") (pintype "bidirectional"))
    )
    (net (code "78") (name "unconnected-(IC9-N{slash}C-Pad4)") (class "Default")
      (node (ref "IC9") (pin "4") (pinfunction "N/C_4") (pintype "bidirectional"))
    )
    (net (code "79") (name "unconnected-(OSC1-STANDBY#-PadP$1)") (class "Default")
      (node (ref "OSC1") (pin "P$1") (pinfunction "STANDBY#_P$1") (pintype "passive"))
    )
    (net (code "80") (name "unconnected-(SV2-Pad3)") (class "Default")
      (node (ref "SV2") (pin "3") (pinfunction "3_3") (pintype "passive"))
    )
    (net (code "81") (name "unconnected-(SV2-Pad4)") (class "Default")
      (node (ref "SV2") (pin "4") (pinfunction "4_4") (pintype "passive"))
    )
    (net (code "82") (name "unconnected-(X2D-S-Pad4)") (class "Default")
      (node (ref "X2") (pin "4") (pinfunction "S_4") (pintype "passive"))
    )
    (net (code "83") (name "unconnected-(X6-4-PadP$4)") (class "Default")
      (node (ref "X6") (pin "P$4") (pinfunction "4_P$4") (pintype "bidirectional"))
    )
    (net (code "84") (name "unconnected-(X6-P$1-PadSHIELD_1)") (class "Default")
      (node (ref "X6") (pin "SHIELD_1") (pinfunction "P$1_SHIELD_1") (pintype "bidirectional"))
    )
    (net (code "85") (name "unconnected-(X6-P$2-PadSHIELD_2)") (class "Default")
      (node (ref "X6") (pin "SHIELD_2") (pinfunction "P$2_SHIELD_2") (pintype "bidirectional"))
    )
  )
)
